# 2_NBU-1012_PCA-10.net
KiCad netlist of a schematic drawn in Altium Designer
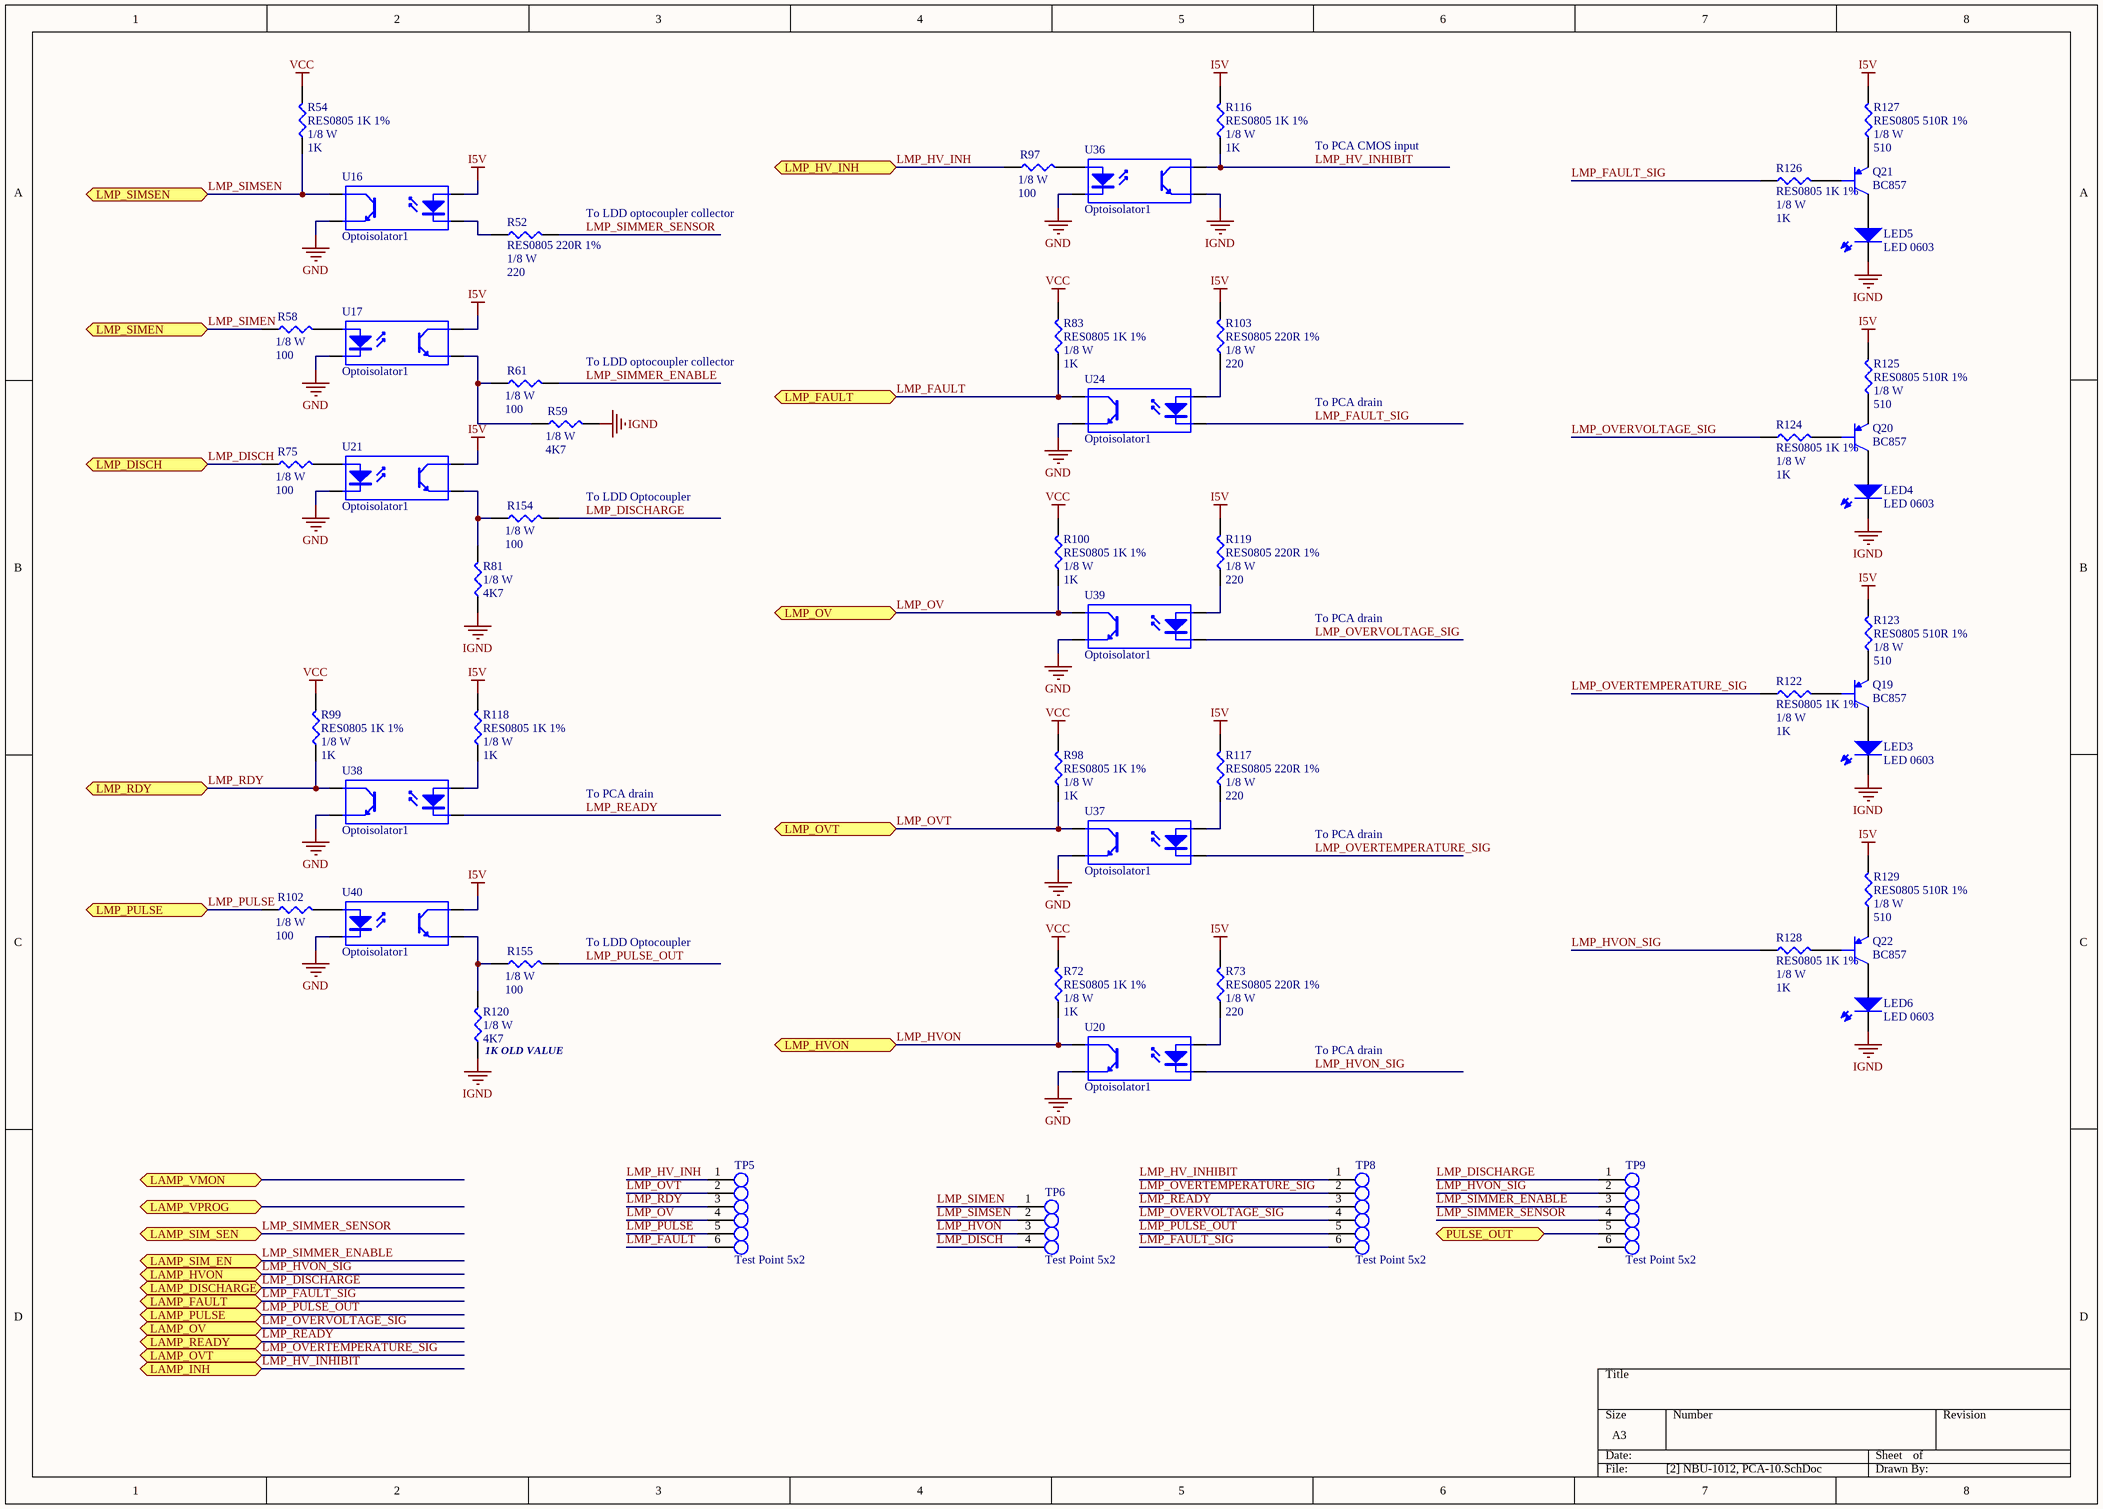
[diagram p0: [2] NBU-1012, PCA-10.SchDoc]

(export (version "E")
  (design (tool "Eeschema 10.0.6"))
  (components
    (comp (ref "LED3") (value "LED 0603") (footprint "PLCC-2") (libsource (lib "LEDs") (part "LED0603")))
    (comp (ref "LED4") (value "LED 0603") (footprint "PLCC-2") (libsource (lib "LEDs") (part "LED0603")))
    (comp (ref "LED5") (value "LED 0603") (footprint "PLCC-2") (libsource (lib "LEDs") (part "LED0603")))
    (comp (ref "LED6") (value "LED 0603") (footprint "PLCC-2") (libsource (lib "LEDs") (part "LED0603")))
    (comp (ref "Q19")
      (value "BC857")
      (footprint "SOT23")
      (description "PNP Transistor")
      (fields (field (name "MANUFACTURER") "NXP") (field (name "MANUFACTURER PART NUMBER") "BC857A.215"))
      (libsource (lib "BJT") (part "BC857"))
    )
    (comp (ref "Q20")
      (value "BC857")
      (footprint "SOT23")
      (description "PNP Transistor")
      (fields (field (name "MANUFACTURER") "NXP") (field (name "MANUFACTURER PART NUMBER") "BC857A.215"))
      (libsource (lib "BJT") (part "BC857"))
    )
    (comp (ref "Q21")
      (value "BC857")
      (footprint "SOT23")
      (description "PNP Transistor")
      (fields (field (name "MANUFACTURER") "NXP") (field (name "MANUFACTURER PART NUMBER") "BC857A.215"))
      (libsource (lib "BJT") (part "BC857"))
    )
    (comp (ref "Q22")
      (value "BC857")
      (footprint "SOT23")
      (description "PNP Transistor")
      (fields (field (name "MANUFACTURER") "NXP") (field (name "MANUFACTURER PART NUMBER") "BC857A.215"))
      (libsource (lib "BJT") (part "BC857"))
    )
    (comp (ref "R52")
      (value "RES0805 220R 1%")
      (footprint "RES0805")
      (description "Think Film Chip resistor")
      (fields
        (field (name "TOLERANCE") "1%")
        (field (name "MANUFACTURER PART NUMBER") "RC0805JR-07220R")
        (field (name "RATING") "1/8 W")
        (field (name "ALTIUM_VALUE") "220")
      )
      (libsource (lib "Resistors") (part "RES0805 220R 1%"))
    )
    (comp (ref "R54")
      (value "RES0805 1K 1%")
      (footprint "RES0805")
      (description "Think Film Chip resistor")
      (fields
        (field (name "TOLERANCE") "1%")
        (field (name "MANUFACTURER PART NUMBER") "RC0805FR-071KL")
        (field (name "RATING") "1/8 W")
        (field (name "ALTIUM_VALUE") "1K")
      )
      (libsource (lib "Resistors") (part "RES0805 1K 1%"))
    )
    (comp (ref "R58")
      (value "100")
      (footprint "RES0805")
      (description "Think Film Chip resistor")
      (fields
        (field (name "TOLERANCE") "1%")
        (field (name "MANUFACTURER PART NUMBER") "RC0805FR-07100RL")
        (field (name "RATING") "1/8 W")
      )
      (libsource (lib "Resistors") (part "RES0805 100R 1%"))
    )
    (comp (ref "R59")
      (value "4K7")
      (footprint "RES0805")
      (description "Think Film Chip resistor")
      (fields
        (field (name "TOLERANCE") "1%")
        (field (name "MANUFACTURER PART NUMBER") "RC0805FR-074K7L")
        (field (name "RATING") "1/8 W")
      )
      (libsource (lib "Resistors") (part "RES0805 4K7 1%"))
    )
    (comp (ref "R61")
      (value "100")
      (footprint "RES0805")
      (description "Think Film Chip resistor")
      (fields
        (field (name "TOLERANCE") "1%")
        (field (name "MANUFACTURER PART NUMBER") "RC0805FR-07100RL")
        (field (name "RATING") "1/8 W")
      )
      (libsource (lib "Resistors") (part "RES0805 100R 1%"))
    )
    (comp (ref "R72")
      (value "RES0805 1K 1%")
      (footprint "RES0805")
      (description "Think Film Chip resistor")
      (fields
        (field (name "TOLERANCE") "1%")
        (field (name "MANUFACTURER PART NUMBER") "RC0805FR-071KL")
        (field (name "RATING") "1/8 W")
        (field (name "ALTIUM_VALUE") "1K")
      )
      (libsource (lib "Resistors") (part "RES0805 1K 1%"))
    )
    (comp (ref "R73")
      (value "RES0805 220R 1%")
      (footprint "RES0805")
      (description "Think Film Chip resistor")
      (fields
        (field (name "TOLERANCE") "1%")
        (field (name "MANUFACTURER PART NUMBER") "RC0805JR-07220R")
        (field (name "RATING") "1/8 W")
        (field (name "ALTIUM_VALUE") "220")
      )
      (libsource (lib "Resistors") (part "RES0805 220R 1%"))
    )
    (comp (ref "R75")
      (value "100")
      (footprint "RES0805")
      (description "Think Film Chip resistor")
      (fields
        (field (name "TOLERANCE") "1%")
        (field (name "MANUFACTURER PART NUMBER") "RC0805FR-07100RL")
        (field (name "RATING") "1/8 W")
      )
      (libsource (lib "Resistors") (part "RES0805 100R 1%"))
    )
    (comp (ref "R81")
      (value "4K7")
      (footprint "RES0805")
      (description "Think Film Chip resistor")
      (fields
        (field (name "TOLERANCE") "1%")
        (field (name "MANUFACTURER PART NUMBER") "RC0805FR-074K7L")
        (field (name "RATING") "1/8 W")
      )
      (libsource (lib "Resistors") (part "RES0805 4K7 1%"))
    )
    (comp (ref "R83")
      (value "RES0805 1K 1%")
      (footprint "RES0805")
      (description "Think Film Chip resistor")
      (fields
        (field (name "TOLERANCE") "1%")
        (field (name "MANUFACTURER PART NUMBER") "RC0805FR-071KL")
        (field (name "RATING") "1/8 W")
        (field (name "ALTIUM_VALUE") "1K")
      )
      (libsource (lib "Resistors") (part "RES0805 1K 1%"))
    )
    (comp (ref "R97")
      (value "100")
      (footprint "RES0805")
      (description "Think Film Chip resistor")
      (fields
        (field (name "TOLERANCE") "1%")
        (field (name "MANUFACTURER PART NUMBER") "RC0805FR-07100RL")
        (field (name "RATING") "1/8 W")
      )
      (libsource (lib "Resistors") (part "RES0805 100R 1%"))
    )
    (comp (ref "R98")
      (value "RES0805 1K 1%")
      (footprint "RES0805")
      (description "Think Film Chip resistor")
      (fields
        (field (name "TOLERANCE") "1%")
        (field (name "MANUFACTURER PART NUMBER") "RC0805FR-071KL")
        (field (name "RATING") "1/8 W")
        (field (name "ALTIUM_VALUE") "1K")
      )
      (libsource (lib "Resistors") (part "RES0805 1K 1%"))
    )
    (comp (ref "R99")
      (value "RES0805 1K 1%")
      (footprint "RES0805")
      (description "Think Film Chip resistor")
      (fields
        (field (name "TOLERANCE") "1%")
        (field (name "MANUFACTURER PART NUMBER") "RC0805FR-071KL")
        (field (name "RATING") "1/8 W")
        (field (name "ALTIUM_VALUE") "1K")
      )
      (libsource (lib "Resistors") (part "RES0805 1K 1%"))
    )
    (comp (ref "R100")
      (value "RES0805 1K 1%")
      (footprint "RES0805")
      (description "Think Film Chip resistor")
      (fields
        (field (name "TOLERANCE") "1%")
        (field (name "MANUFACTURER PART NUMBER") "RC0805FR-071KL")
        (field (name "RATING") "1/8 W")
        (field (name "ALTIUM_VALUE") "1K")
      )
      (libsource (lib "Resistors") (part "RES0805 1K 1%"))
    )
    (comp (ref "R102")
      (value "100")
      (footprint "RES0805")
      (description "Think Film Chip resistor")
      (fields
        (field (name "TOLERANCE") "1%")
        (field (name "MANUFACTURER PART NUMBER") "RC0805FR-07100RL")
        (field (name "RATING") "1/8 W")
      )
      (libsource (lib "Resistors") (part "RES0805 100R 1%"))
    )
    (comp (ref "R103")
      (value "RES0805 220R 1%")
      (footprint "RES0805")
      (description "Think Film Chip resistor")
      (fields
        (field (name "TOLERANCE") "1%")
        (field (name "MANUFACTURER PART NUMBER") "RC0805JR-07220R")
        (field (name "RATING") "1/8 W")
        (field (name "ALTIUM_VALUE") "220")
      )
      (libsource (lib "Resistors") (part "RES0805 220R 1%"))
    )
    (comp (ref "R116")
      (value "RES0805 1K 1%")
      (footprint "RES0805")
      (description "Think Film Chip resistor")
      (fields
        (field (name "TOLERANCE") "1%")
        (field (name "MANUFACTURER PART NUMBER") "RC0805FR-071KL")
        (field (name "RATING") "1/8 W")
        (field (name "ALTIUM_VALUE") "1K")
      )
      (libsource (lib "Resistors") (part "RES0805 1K 1%"))
    )
    (comp (ref "R117")
      (value "RES0805 220R 1%")
      (footprint "RES0805")
      (description "Think Film Chip resistor")
      (fields
        (field (name "TOLERANCE") "1%")
        (field (name "MANUFACTURER PART NUMBER") "RC0805JR-07220R")
        (field (name "RATING") "1/8 W")
        (field (name "ALTIUM_VALUE") "220")
      )
      (libsource (lib "Resistors") (part "RES0805 220R 1%"))
    )
    (comp (ref "R118")
      (value "RES0805 1K 1%")
      (footprint "RES0805")
      (description "Think Film Chip resistor")
      (fields
        (field (name "TOLERANCE") "1%")
        (field (name "MANUFACTURER PART NUMBER") "RC0805FR-071KL")
        (field (name "RATING") "1/8 W")
        (field (name "ALTIUM_VALUE") "1K")
      )
      (libsource (lib "Resistors") (part "RES0805 1K 1%"))
    )
    (comp (ref "R119")
      (value "RES0805 220R 1%")
      (footprint "RES0805")
      (description "Think Film Chip resistor")
      (fields
        (field (name "TOLERANCE") "1%")
        (field (name "MANUFACTURER PART NUMBER") "RC0805JR-07220R")
        (field (name "RATING") "1/8 W")
        (field (name "ALTIUM_VALUE") "220")
      )
      (libsource (lib "Resistors") (part "RES0805 220R 1%"))
    )
    (comp (ref "R120")
      (value "4K7")
      (footprint "RES0805")
      (description "Think Film Chip resistor")
      (fields
        (field (name "TOLERANCE") "1%")
        (field (name "MANUFACTURER PART NUMBER") "RC0805FR-074K7L")
        (field (name "RATING") "1/8 W")
      )
      (libsource (lib "Resistors") (part "RES0805 4K7 1%"))
    )
    (comp (ref "R122")
      (value "RES0805 1K 1%")
      (footprint "RES0805")
      (description "Think Film Chip resistor")
      (fields
        (field (name "TOLERANCE") "1%")
        (field (name "MANUFACTURER PART NUMBER") "RC0805FR-071KL")
        (field (name "RATING") "1/8 W")
        (field (name "ALTIUM_VALUE") "1K")
      )
      (libsource (lib "Resistors") (part "RES0805 1K 1%"))
    )
    (comp (ref "R123")
      (value "RES0805 510R 1%")
      (footprint "RES0805")
      (description "Think Film Chip resistor")
      (fields
        (field (name "TOLERANCE") "1%")
        (field (name "MANUFACTURER PART NUMBER") "RC0805FR-07510RL")
        (field (name "RATING") "1/8 W")
        (field (name "ALTIUM_VALUE") "510")
      )
      (libsource (lib "Resistors") (part "RES0805 510R 1%"))
    )
    (comp (ref "R124")
      (value "RES0805 1K 1%")
      (footprint "RES0805")
      (description "Think Film Chip resistor")
      (fields
        (field (name "TOLERANCE") "1%")
        (field (name "MANUFACTURER PART NUMBER") "RC0805FR-071KL")
        (field (name "RATING") "1/8 W")
        (field (name "ALTIUM_VALUE") "1K")
      )
      (libsource (lib "Resistors") (part "RES0805 1K 1%"))
    )
    (comp (ref "R125")
      (value "RES0805 510R 1%")
      (footprint "RES0805")
      (description "Think Film Chip resistor")
      (fields
        (field (name "TOLERANCE") "1%")
        (field (name "MANUFACTURER PART NUMBER") "RC0805FR-07510RL")
        (field (name "RATING") "1/8 W")
        (field (name "ALTIUM_VALUE") "510")
      )
      (libsource (lib "Resistors") (part "RES0805 510R 1%"))
    )
    (comp (ref "R126")
      (value "RES0805 1K 1%")
      (footprint "RES0805")
      (description "Think Film Chip resistor")
      (fields
        (field (name "TOLERANCE") "1%")
        (field (name "MANUFACTURER PART NUMBER") "RC0805FR-071KL")
        (field (name "RATING") "1/8 W")
        (field (name "ALTIUM_VALUE") "1K")
      )
      (libsource (lib "Resistors") (part "RES0805 1K 1%"))
    )
    (comp (ref "R127")
      (value "RES0805 510R 1%")
      (footprint "RES0805")
      (description "Think Film Chip resistor")
      (fields
        (field (name "TOLERANCE") "1%")
        (field (name "MANUFACTURER PART NUMBER") "RC0805FR-07510RL")
        (field (name "RATING") "1/8 W")
        (field (name "ALTIUM_VALUE") "510")
      )
      (libsource (lib "Resistors") (part "RES0805 510R 1%"))
    )
    (comp (ref "R128")
      (value "RES0805 1K 1%")
      (footprint "RES0805")
      (description "Think Film Chip resistor")
      (fields
        (field (name "TOLERANCE") "1%")
        (field (name "MANUFACTURER PART NUMBER") "RC0805FR-071KL")
        (field (name "RATING") "1/8 W")
        (field (name "ALTIUM_VALUE") "1K")
      )
      (libsource (lib "Resistors") (part "RES0805 1K 1%"))
    )
    (comp (ref "R129")
      (value "RES0805 510R 1%")
      (footprint "RES0805")
      (description "Think Film Chip resistor")
      (fields
        (field (name "TOLERANCE") "1%")
        (field (name "MANUFACTURER PART NUMBER") "RC0805FR-07510RL")
        (field (name "RATING") "1/8 W")
        (field (name "ALTIUM_VALUE") "510")
      )
      (libsource (lib "Resistors") (part "RES0805 510R 1%"))
    )
    (comp (ref "R154")
      (value "100")
      (footprint "RES0805")
      (description "Think Film Chip resistor")
      (fields
        (field (name "TOLERANCE") "1%")
        (field (name "MANUFACTURER PART NUMBER") "RC0805FR-07100RL")
        (field (name "RATING") "1/8 W")
      )
      (libsource (lib "Resistors") (part "RES0805 100R 1%"))
    )
    (comp (ref "R155")
      (value "100")
      (footprint "RES0805")
      (description "Think Film Chip resistor")
      (fields
        (field (name "TOLERANCE") "1%")
        (field (name "MANUFACTURER PART NUMBER") "RC0805FR-07100RL")
        (field (name "RATING") "1/8 W")
      )
      (libsource (lib "Resistors") (part "RES0805 100R 1%"))
    )
    (comp (ref "TP5")
      (value "Test Point 5x2")
      (footprint "PG-1.5-13.5-6P-2.54PH")
      (libsource (lib "Connectors") (part "PG-1.5-13.5-6P-2.54PH"))
    )
    (comp (ref "TP6")
      (value "Test Point 5x2")
      (footprint "PG-1.5-13.5-4P-2.54PH")
      (libsource (lib "Connectors") (part "PG-1.5-13.5-4P-2.54PH"))
    )
    (comp (ref "TP8")
      (value "Test Point 5x2")
      (footprint "PG-1.5-13.5-6P-2.54PH")
      (libsource (lib "Connectors") (part "PG-1.5-13.5-6P-2.54PH"))
    )
    (comp (ref "TP9")
      (value "Test Point 5x2")
      (footprint "PG-1.5-13.5-6P-2.54PH")
      (libsource (lib "Connectors") (part "PG-1.5-13.5-6P-2.54PH"))
    )
    (comp (ref "U16")
      (value "Optoisolator1")
      (footprint "DIP-4")
      (description "4-Pin Phototransistor Optocoupler")
      (fields (field (name "PUBLISHER") "Altium Limited"))
      (libsource (lib "Miscellaneous Devices") (part "Optoisolator1"))
    )
    (comp (ref "U17")
      (value "Optoisolator1")
      (footprint "DIP-4")
      (description "4-Pin Phototransistor Optocoupler")
      (fields (field (name "PUBLISHER") "Altium Limited"))
      (libsource (lib "Miscellaneous Devices") (part "Optoisolator1"))
    )
    (comp (ref "U20")
      (value "Optoisolator1")
      (footprint "DIP-4")
      (description "4-Pin Phototransistor Optocoupler")
      (fields (field (name "PUBLISHER") "Altium Limited"))
      (libsource (lib "Miscellaneous Devices") (part "Optoisolator1"))
    )
    (comp (ref "U21")
      (value "Optoisolator1")
      (footprint "DIP-4")
      (description "4-Pin Phototransistor Optocoupler")
      (fields (field (name "PUBLISHER") "Altium Limited"))
      (libsource (lib "Miscellaneous Devices") (part "Optoisolator1"))
    )
    (comp (ref "U24")
      (value "Optoisolator1")
      (footprint "DIP-4")
      (description "4-Pin Phototransistor Optocoupler")
      (fields (field (name "PUBLISHER") "Altium Limited"))
      (libsource (lib "Miscellaneous Devices") (part "Optoisolator1"))
    )
    (comp (ref "U36")
      (value "Optoisolator1")
      (footprint "DIP-4")
      (description "4-Pin Phototransistor Optocoupler")
      (fields (field (name "PUBLISHER") "Altium Limited"))
      (libsource (lib "Miscellaneous Devices") (part "Optoisolator1"))
    )
    (comp (ref "U37")
      (value "Optoisolator1")
      (footprint "DIP-4")
      (description "4-Pin Phototransistor Optocoupler")
      (fields (field (name "PUBLISHER") "Altium Limited"))
      (libsource (lib "Miscellaneous Devices") (part "Optoisolator1"))
    )
    (comp (ref "U38")
      (value "Optoisolator1")
      (footprint "DIP-4")
      (description "4-Pin Phototransistor Optocoupler")
      (fields (field (name "PUBLISHER") "Altium Limited"))
      (libsource (lib "Miscellaneous Devices") (part "Optoisolator1"))
    )
    (comp (ref "U39")
      (value "Optoisolator1")
      (footprint "DIP-4")
      (description "4-Pin Phototransistor Optocoupler")
      (fields (field (name "PUBLISHER") "Altium Limited"))
      (libsource (lib "Miscellaneous Devices") (part "Optoisolator1"))
    )
    (comp (ref "U40")
      (value "Optoisolator1")
      (footprint "DIP-4")
      (description "4-Pin Phototransistor Optocoupler")
      (fields (field (name "PUBLISHER") "Altium Limited"))
      (libsource (lib "Miscellaneous Devices") (part "Optoisolator1"))
    )
  )
  (nets
    (net (code "3") (name "/LMP_DISCH") (class "Default")
      (node (ref "R75") (pin "1") (pintype "passive"))
      (node (ref "TP6") (pin "4") (pinfunction "4_4") (pintype "passive"))
    )
    (net (code "4") (name "/LMP_DISCHARGE") (class "Default")
      (node (ref "R154") (pin "2") (pintype "passive"))
      (node (ref "TP9") (pin "1") (pinfunction "1_1") (pintype "passive"))
    )
    (net (code "5") (name "/LMP_FAULT") (class "Default")
      (node (ref "R83") (pin "1") (pintype "passive"))
      (node (ref "TP5") (pin "6") (pinfunction "6_6") (pintype "passive"))
      (node (ref "U24") (pin "4") (pinfunction "C_4") (pintype "passive"))
    )
    (net (code "6") (name "/LMP_FAULT_SIG") (class "Default")
      (node (ref "R126") (pin "1") (pintype "passive"))
      (node (ref "TP8") (pin "6") (pinfunction "6_6") (pintype "passive"))
      (node (ref "U24") (pin "2") (pinfunction "K_2") (pintype "passive"))
    )
    (net (code "7") (name "/LMP_HVON") (class "Default")
      (node (ref "R72") (pin "1") (pintype "passive"))
      (node (ref "TP6") (pin "3") (pinfunction "3_3") (pintype "passive"))
      (node (ref "U20") (pin "4") (pinfunction "C_4") (pintype "passive"))
    )
    (net (code "8") (name "/LMP_HVON_SIG") (class "Default")
      (node (ref "R128") (pin "1") (pintype "passive"))
      (node (ref "TP9") (pin "2") (pinfunction "2_2") (pintype "passive"))
      (node (ref "U20") (pin "2") (pinfunction "K_2") (pintype "passive"))
    )
    (net (code "9") (name "/LMP_HV_INH") (class "Default")
      (node (ref "R97") (pin "1") (pintype "passive"))
      (node (ref "TP5") (pin "1") (pinfunction "1_1") (pintype "passive"))
    )
    (net (code "10") (name "/LMP_HV_INHIBIT") (class "Default")
      (node (ref "R116") (pin "1") (pintype "passive"))
      (node (ref "TP8") (pin "1") (pinfunction "1_1") (pintype "passive"))
      (node (ref "U36") (pin "4") (pinfunction "C_4") (pintype "passive"))
    )
    (net (code "11") (name "/LMP_OV") (class "Default")
      (node (ref "R100") (pin "1") (pintype "passive"))
      (node (ref "TP5") (pin "4") (pinfunction "4_4") (pintype "passive"))
      (node (ref "U39") (pin "4") (pinfunction "C_4") (pintype "passive"))
    )
    (net (code "12") (name "/LMP_OVERTEMPERATURE_SIG") (class "Default")
      (node (ref "R122") (pin "1") (pintype "passive"))
      (node (ref "TP8") (pin "2") (pinfunction "2_2") (pintype "passive"))
      (node (ref "U37") (pin "2") (pinfunction "K_2") (pintype "passive"))
    )
    (net (code "13") (name "/LMP_OVERVOLTAGE_SIG") (class "Default")
      (node (ref "R124") (pin "1") (pintype "passive"))
      (node (ref "TP8") (pin "4") (pinfunction "4_4") (pintype "passive"))
      (node (ref "U39") (pin "2") (pinfunction "K_2") (pintype "passive"))
    )
    (net (code "14") (name "/LMP_OVT") (class "Default")
      (node (ref "R98") (pin "1") (pintype "passive"))
      (node (ref "TP5") (pin "2") (pinfunction "2_2") (pintype "passive"))
      (node (ref "U37") (pin "4") (pinfunction "C_4") (pintype "passive"))
    )
    (net (code "15") (name "/LMP_PULSE") (class "Default")
      (node (ref "R102") (pin "1") (pintype "passive"))
      (node (ref "TP5") (pin "5") (pinfunction "5_5") (pintype "passive"))
    )
    (net (code "16") (name "/LMP_PULSE_OUT") (class "Default")
      (node (ref "R155") (pin "2") (pintype "passive"))
      (node (ref "TP8") (pin "5") (pinfunction "5_5") (pintype "passive"))
    )
    (net (code "17") (name "/LMP_RDY") (class "Default")
      (node (ref "R99") (pin "1") (pintype "passive"))
      (node (ref "TP5") (pin "3") (pinfunction "3_3") (pintype "passive"))
      (node (ref "U38") (pin "4") (pinfunction "C_4") (pintype "passive"))
    )
    (net (code "18") (name "/LMP_READY") (class "Default")
      (node (ref "TP8") (pin "3") (pinfunction "3_3") (pintype "passive"))
      (node (ref "U38") (pin "2") (pinfunction "K_2") (pintype "passive"))
    )
    (net (code "19") (name "/LMP_SIMEN") (class "Default")
      (node (ref "R58") (pin "1") (pintype "passive"))
      (node (ref "TP6") (pin "1") (pinfunction "1_1") (pintype "passive"))
    )
    (net (code "20") (name "/LMP_SIMMER_ENABLE") (class "Default")
      (node (ref "R61") (pin "2") (pintype "passive"))
      (node (ref "TP9") (pin "3") (pinfunction "3_3") (pintype "passive"))
    )
    (net (code "21") (name "/LMP_SIMMER_SENSOR") (class "Default")
      (node (ref "R52") (pin "2") (pintype "passive"))
      (node (ref "TP9") (pin "4") (pinfunction "4_4") (pintype "passive"))
    )
    (net (code "22") (name "/LMP_SIMSEN") (class "Default")
      (node (ref "R54") (pin "1") (pintype "passive"))
      (node (ref "TP6") (pin "2") (pinfunction "2_2") (pintype "passive"))
      (node (ref "U16") (pin "4") (pinfunction "C_4") (pintype "passive"))
    )
    (net (code "23") (name "/PULSE_OUT") (class "Default")
      (node (ref "TP9") (pin "5") (pinfunction "5_5") (pintype "passive"))
    )
    (net (code "24") (name "GND") (class "Default")
      (node (ref "U16") (pin "3") (pinfunction "E_3") (pintype "passive"))
      (node (ref "U17") (pin "2") (pinfunction "K_2") (pintype "passive"))
      (node (ref "U20") (pin "3") (pinfunction "E_3") (pintype "passive"))
      (node (ref "U21") (pin "2") (pinfunction "K_2") (pintype "passive"))
      (node (ref "U24") (pin "3") (pinfunction "E_3") (pintype "passive"))
      (node (ref "U36") (pin "2") (pinfunction "K_2") (pintype "passive"))
      (node (ref "U37") (pin "3") (pinfunction "E_3") (pintype "passive"))
      (node (ref "U38") (pin "3") (pinfunction "E_3") (pintype "passive"))
      (node (ref "U39") (pin "3") (pinfunction "E_3") (pintype "passive"))
      (node (ref "U40") (pin "2") (pinfunction "K_2") (pintype "passive"))
    )
    (net (code "25") (name "I5V") (class "Default")
      (node (ref "R103") (pin "2") (pintype "passive"))
      (node (ref "R116") (pin "2") (pintype "passive"))
      (node (ref "R117") (pin "2") (pintype "passive"))
      (node (ref "R118") (pin "2") (pintype "passive"))
      (node (ref "R119") (pin "2") (pintype "passive"))
      (node (ref "R123") (pin "2") (pintype "passive"))
      (node (ref "R125") (pin "2") (pintype "passive"))
      (node (ref "R127") (pin "2") (pintype "passive"))
      (node (ref "R129") (pin "2") (pintype "passive"))
      (node (ref "R73") (pin "2") (pintype "passive"))
      (node (ref "U16") (pin "1") (pinfunction "A_1") (pintype "passive"))
      (node (ref "U17") (pin "4") (pinfunction "C_4") (pintype "passive"))
      (node (ref "U21") (pin "4") (pinfunction "C_4") (pintype "passive"))
      (node (ref "U40") (pin "4") (pinfunction "C_4") (pintype "passive"))
    )
    (net (code "26") (name "IGND") (class "Default")
      (node (ref "LED3") (pin "1") (pinfunction "1_1") (pintype "passive"))
      (node (ref "LED4") (pin "1") (pinfunction "1_1") (pintype "passive"))
      (node (ref "LED5") (pin "1") (pinfunction "1_1") (pintype "passive"))
      (node (ref "LED6") (pin "1") (pinfunction "1_1") (pintype "passive"))
      (node (ref "R120") (pin "1") (pintype "passive"))
      (node (ref "R59") (pin "2") (pintype "passive"))
      (node (ref "R81") (pin "1") (pintype "passive"))
      (node (ref "U36") (pin "3") (pinfunction "E_3") (pintype "passive"))
    )
    (net (code "27") (name "Net-(LED3-Pad2)") (class "Default")
      (node (ref "LED3") (pin "2") (pinfunction "2_2") (pintype "passive"))
      (node (ref "Q19") (pin "3") (pinfunction "3_3") (pintype "passive"))
    )
    (net (code "28") (name "Net-(LED4-Pad2)") (class "Default")
      (node (ref "LED4") (pin "2") (pinfunction "2_2") (pintype "passive"))
      (node (ref "Q20") (pin "3") (pinfunction "3_3") (pintype "passive"))
    )
    (net (code "29") (name "Net-(LED5-Pad2)") (class "Default")
      (node (ref "LED5") (pin "2") (pinfunction "2_2") (pintype "passive"))
      (node (ref "Q21") (pin "3") (pinfunction "3_3") (pintype "passive"))
    )
    (net (code "30") (name "Net-(LED6-Pad2)") (class "Default")
      (node (ref "LED6") (pin "2") (pinfunction "2_2") (pintype "passive"))
      (node (ref "Q22") (pin "3") (pinfunction "3_3") (pintype "passive"))
    )
    (net (code "31") (name "Net-(Q19-Pad1)") (class "Default")
      (node (ref "Q19") (pin "1") (pinfunction "1_1") (pintype "passive"))
      (node (ref "R122") (pin "2") (pintype "passive"))
    )
    (net (code "32") (name "Net-(Q19-Pad2)") (class "Default")
      (node (ref "Q19") (pin "2") (pinfunction "2_2") (pintype "passive"))
      (node (ref "R123") (pin "1") (pintype "passive"))
    )
    (net (code "33") (name "Net-(Q20-Pad1)") (class "Default")
      (node (ref "Q20") (pin "1") (pinfunction "1_1") (pintype "passive"))
      (node (ref "R124") (pin "2") (pintype "passive"))
    )
    (net (code "34") (name "Net-(Q20-Pad2)") (class "Default")
      (node (ref "Q20") (pin "2") (pinfunction "2_2") (pintype "passive"))
      (node (ref "R125") (pin "1") (pintype "passive"))
    )
    (net (code "35") (name "Net-(Q21-Pad1)") (class "Default")
      (node (ref "Q21") (pin "1") (pinfunction "1_1") (pintype "passive"))
      (node (ref "R126") (pin "2") (pintype "passive"))
    )
    (net (code "36") (name "Net-(Q21-Pad2)") (class "Default")
      (node (ref "Q21") (pin "2") (pinfunction "2_2") (pintype "passive"))
      (node (ref "R127") (pin "1") (pintype "passive"))
    )
    (net (code "37") (name "Net-(Q22-Pad1)") (class "Default")
      (node (ref "Q22") (pin "1") (pinfunction "1_1") (pintype "passive"))
      (node (ref "R128") (pin "2") (pintype "passive"))
    )
    (net (code "38") (name "Net-(Q22-Pad2)") (class "Default")
      (node (ref "Q22") (pin "2") (pinfunction "2_2") (pintype "passive"))
      (node (ref "R129") (pin "1") (pintype "passive"))
    )
    (net (code "39") (name "Net-(U16-K)") (class "Default")
      (node (ref "R52") (pin "1") (pintype "passive"))
      (node (ref "U16") (pin "2") (pinfunction "K_2") (pintype "passive"))
    )
    (net (code "40") (name "Net-(U17-A)") (class "Default")
      (node (ref "R58") (pin "2") (pintype "passive"))
      (node (ref "U17") (pin "1") (pinfunction "A_1") (pintype "passive"))
    )
    (net (code "41") (name "Net-(U17-E)") (class "Default")
      (node (ref "R59") (pin "1") (pintype "passive"))
      (node (ref "R61") (pin "1") (pintype "passive"))
      (node (ref "U17") (pin "3") (pinfunction "E_3") (pintype "passive"))
    )
    (net (code "42") (name "Net-(U20-A)") (class "Default")
      (node (ref "R73") (pin "1") (pintype "passive"))
      (node (ref "U20") (pin "1") (pinfunction "A_1") (pintype "passive"))
    )
    (net (code "43") (name "Net-(U21-A)") (class "Default")
      (node (ref "R75") (pin "2") (pintype "passive"))
      (node (ref "U21") (pin "1") (pinfunction "A_1") (pintype "passive"))
    )
    (net (code "44") (name "Net-(U21-E)") (class "Default")
      (node (ref "R154") (pin "1") (pintype "passive"))
      (node (ref "R81") (pin "2") (pintype "passive"))
      (node (ref "U21") (pin "3") (pinfunction "E_3") (pintype "passive"))
    )
    (net (code "45") (name "Net-(U24-A)") (class "Default")
      (node (ref "R103") (pin "1") (pintype "passive"))
      (node (ref "U24") (pin "1") (pinfunction "A_1") (pintype "passive"))
    )
    (net (code "46") (name "Net-(U36-A)") (class "Default")
      (node (ref "R97") (pin "2") (pintype "passive"))
      (node (ref "U36") (pin "1") (pinfunction "A_1") (pintype "passive"))
    )
    (net (code "47") (name "Net-(U37-A)") (class "Default")
      (node (ref "R117") (pin "1") (pintype "passive"))
      (node (ref "U37") (pin "1") (pinfunction "A_1") (pintype "passive"))
    )
    (net (code "48") (name "Net-(U38-A)") (class "Default")
      (node (ref "R118") (pin "1") (pintype "passive"))
      (node (ref "U38") (pin "1") (pinfunction "A_1") (pintype "passive"))
    )
    (net (code "49") (name "Net-(U39-A)") (class "Default")
      (node (ref "R119") (pin "1") (pintype "passive"))
      (node (ref "U39") (pin "1") (pinfunction "A_1") (pintype "passive"))
    )
    (net (code "50") (name "Net-(U40-A)") (class "Default")
      (node (ref "R102") (pin "2") (pintype "passive"))
      (node (ref "U40") (pin "1") (pinfunction "A_1") (pintype "passive"))
    )
    (net (code "51") (name "Net-(U40-E)") (class "Default")
      (node (ref "R120") (pin "2") (pintype "passive"))
      (node (ref "R155") (pin "1") (pintype "passive"))
      (node (ref "U40") (pin "3") (pinfunction "E_3") (pintype "passive"))
    )
    (net (code "52") (name "VCC") (class "Default")
      (node (ref "R100") (pin "2") (pintype "passive"))
      (node (ref "R54") (pin "2") (pintype "passive"))
      (node (ref "R72") (pin "2") (pintype "passive"))
      (node (ref "R83") (pin "2") (pintype "passive"))
      (node (ref "R98") (pin "2") (pintype "passive"))
      (node (ref "R99") (pin "2") (pintype "passive"))
    )
    (net (code "53") (name "unconnected-(TP9-Pad6)") (class "Default")
      (node (ref "TP9") (pin "6") (pinfunction "6_6") (pintype "passive"))
    )
  )
)
